# CMWX_LoRa_GPS_v14.net
KiCad netlist of a schematic drawn in EAGLE
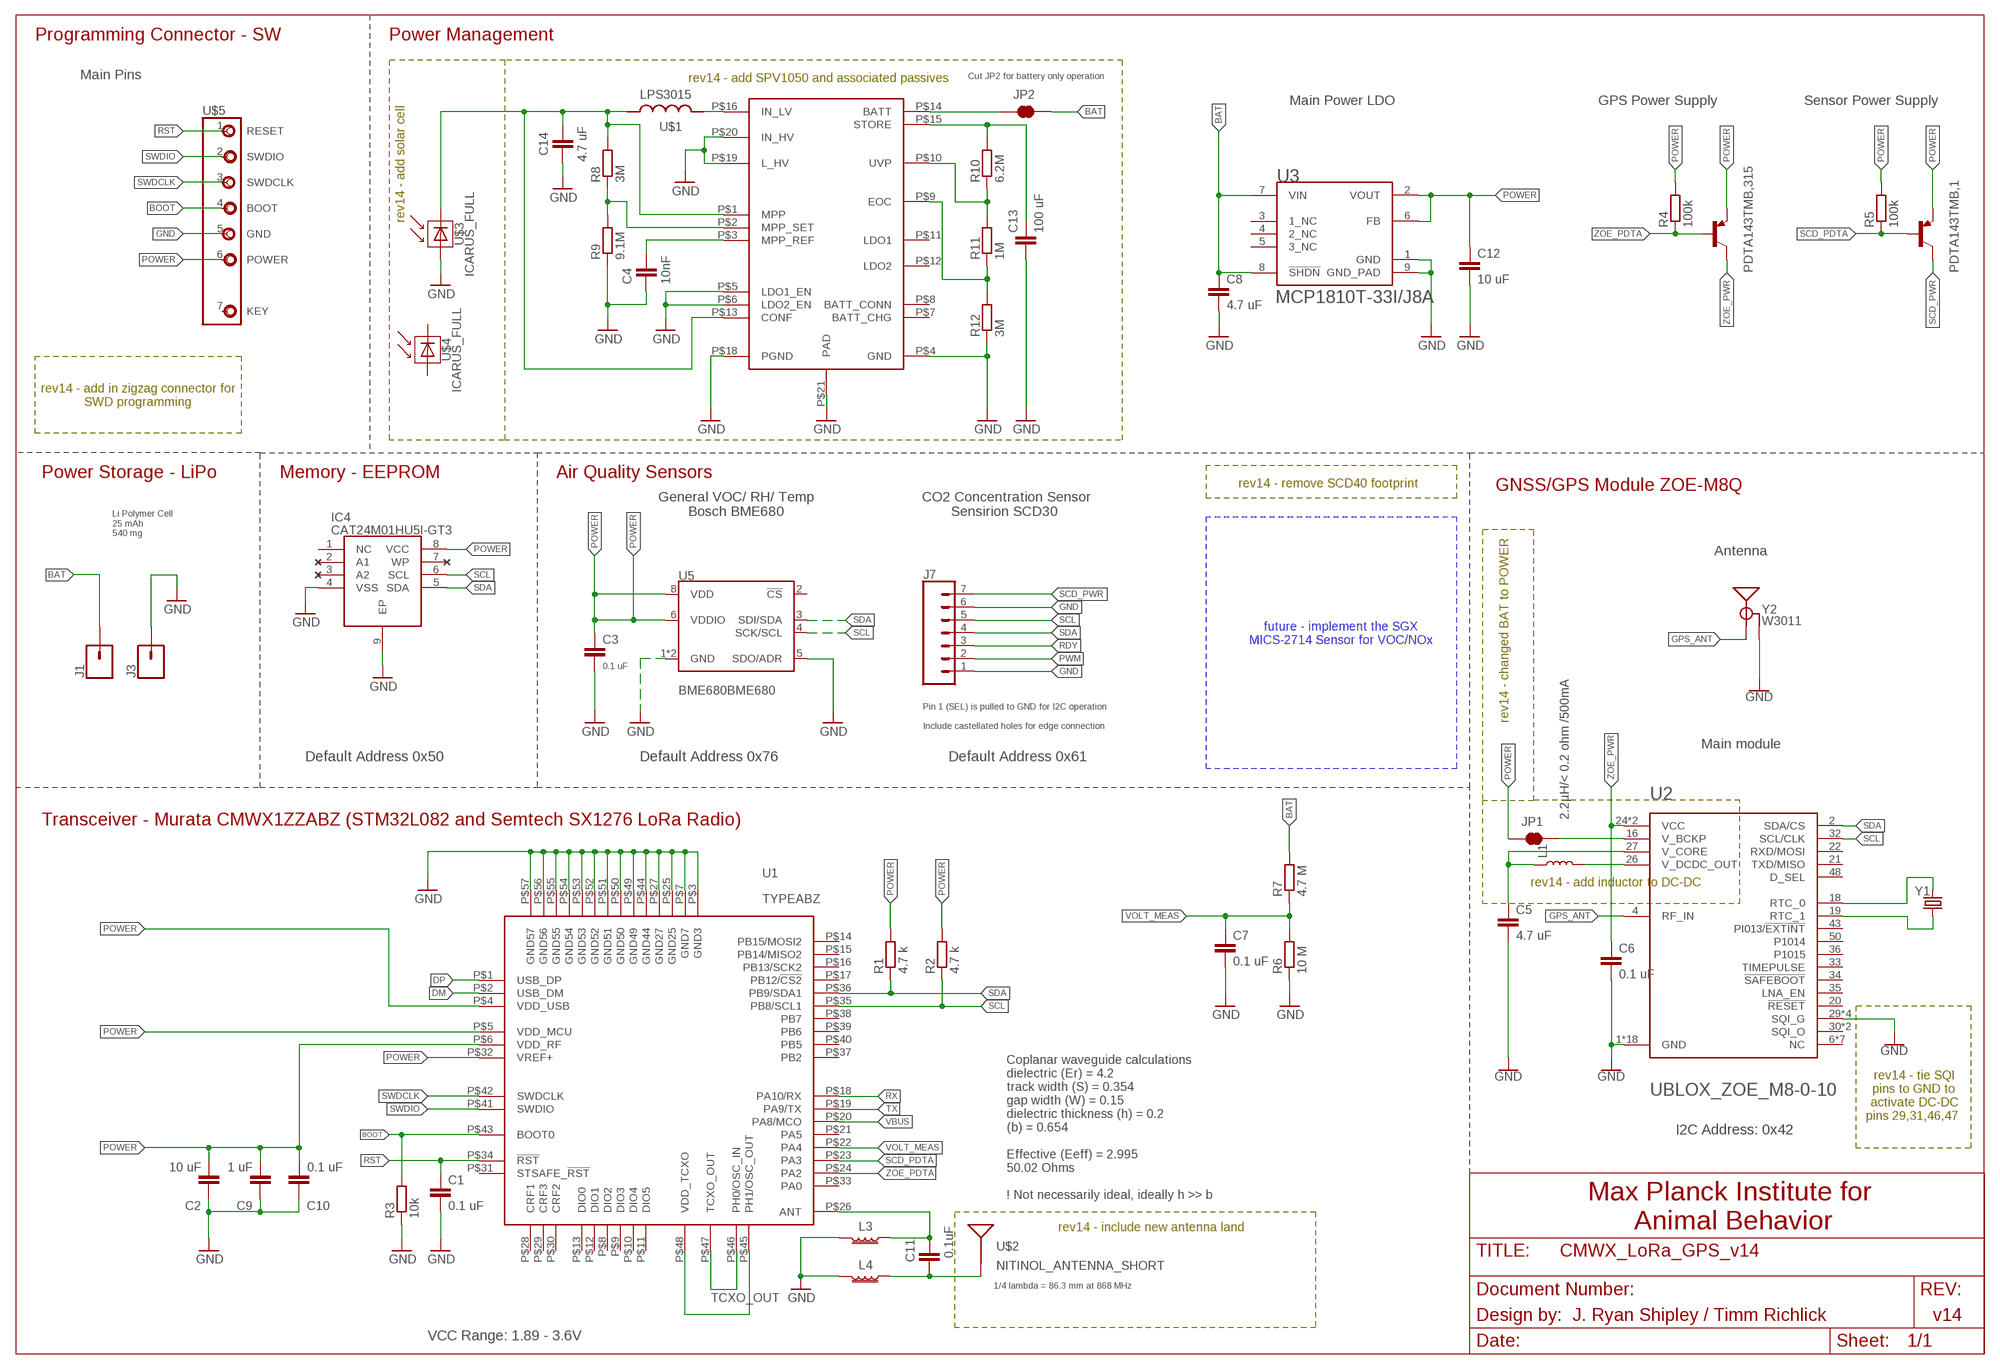
[diagram p0: schematic, sheet 1]

(export (version "E")
  (design (tool "Eeschema 10.0.6"))
  (components
    (comp (ref "C1")
      (value "0.1 uF")
      (footprint "eagle-import:C0201")
      (libsource (lib "eagle-import") (part "C-EUC0201"))
    )
    (comp (ref "C2")
      (value "10 uF")
      (footprint "eagle-import:C0201")
      (libsource (lib "eagle-import") (part "C-EUC0201"))
    )
    (comp (ref "C3")
      (value "0.1 uF")
      (footprint "eagle-import:C0201")
      (libsource (lib "eagle-import") (part "C-EUC0201"))
    )
    (comp (ref "C4")
      (value "10nF")
      (footprint "eagle-import:C0201")
      (libsource (lib "eagle-import") (part "C-EUC0201"))
    )
    (comp (ref "C5")
      (value "4.7 uF")
      (footprint "eagle-import:C0201")
      (libsource (lib "eagle-import") (part "C-EUC0201"))
    )
    (comp (ref "C6")
      (value "0.1 uF")
      (footprint "eagle-import:C0201")
      (libsource (lib "eagle-import") (part "C-EUC0201"))
    )
    (comp (ref "C7")
      (value "0.1 uF")
      (footprint "eagle-import:C0201")
      (libsource (lib "eagle-import") (part "C-EUC0201"))
    )
    (comp (ref "C8")
      (value "4.7 uF")
      (footprint "eagle-import:C0201")
      (libsource (lib "eagle-import") (part "C-EUC0201"))
    )
    (comp (ref "C9")
      (value "1 uF")
      (footprint "eagle-import:C0201")
      (libsource (lib "eagle-import") (part "C-EUC0201"))
    )
    (comp (ref "C10")
      (value "0.1 uF")
      (footprint "eagle-import:C0201")
      (libsource (lib "eagle-import") (part "C-EUC0201"))
    )
    (comp (ref "C11")
      (value "0.1uF")
      (footprint "eagle-import:0402-TIGHT")
      (libsource (lib "eagle-import") (part "0.1UF-0402T-16V-10%"))
    )
    (comp (ref "C12")
      (value "10 uF")
      (footprint "eagle-import:C0201")
      (libsource (lib "eagle-import") (part "C-EUC0201"))
    )
    (comp (ref "C13")
      (value "100 uF")
      (footprint "eagle-import:C0201")
      (libsource (lib "eagle-import") (part "C-EUC0201"))
    )
    (comp (ref "C14")
      (value "4.7 uF")
      (footprint "eagle-import:C0201")
      (libsource (lib "eagle-import") (part "C-EUC0201"))
    )
    (comp (ref "IC4")
      (value "CAT24M01HU5I-GT3")
      (footprint "eagle-import:SON50P300X200X55-9N")
      (fields
        (field (name "MOUSER_PART_NUMBER") "863-CAT24M01HU5I-GT3")
        (field (name "RS_PART_NUMBER") "7814831P")
      )
      (libsource (lib "eagle-import") (part "CAT24M01HU5I-GT3"))
    )
    (comp (ref "J1")
      (value "CONN_01PTH_NO_SILK_YES_STOP")
      (footprint "eagle-import:1X01_NO_SILK")
      (libsource (lib "eagle-import") (part "CONN_01PTH_NO_SILK_YES_STOP"))
    )
    (comp (ref "J3")
      (value "CONN_01PTH_NO_SILK_YES_STOP")
      (footprint "eagle-import:1X01_NO_SILK")
      (libsource (lib "eagle-import") (part "CONN_01PTH_NO_SILK_YES_STOP"))
    )
    (comp (ref "J7")
      (value "CONN_07NO_SILK")
      (footprint "eagle-import:1X07_NO_SILK")
      (libsource (lib "eagle-import") (part "CONN_07NO_SILK"))
    )
    (comp (ref "JP1")
      (value "JUMPER-SMT_2_NC_TRACE_NO-SILK")
      (footprint "eagle-import:SMT-JUMPER_2_NC_TRACE_NO-SILK")
      (libsource (lib "eagle-import") (part "JUMPER-SMT_2_NC_TRACE_NO-SILK"))
    )
    (comp (ref "JP2")
      (value "JUMPER-SMT_2_NC_TRACE_NO-SILK")
      (footprint "eagle-import:SMT-JUMPER_2_NC_TRACE_NO-SILK")
      (libsource (lib "eagle-import") (part "JUMPER-SMT_2_NC_TRACE_NO-SILK"))
    )
    (comp (ref "L1")
      (value "2.2µH/< 0.2 ohm /500mA")
      (footprint "eagle-import:0805")
      (libsource (lib "eagle-import") (part "INDUCTOR-0805-3.3UH"))
    )
    (comp (ref "L3")
      (value "FERRITE_BEAD-120_OHM_TIGHT")
      (footprint "eagle-import:0402-TIGHT")
      (libsource (lib "eagle-import") (part "FERRITE_BEAD-120_OHM_TIGHT"))
    )
    (comp (ref "L4")
      (value "FERRITE_BEAD-120_OHM_TIGHT")
      (footprint "eagle-import:0402-TIGHT")
      (libsource (lib "eagle-import") (part "FERRITE_BEAD-120_OHM_TIGHT"))
    )
    (comp (ref "PDTA143TMB,1")
      (value "TINYPICO-PNPAMB")
      (footprint "eagle-import:SOT883(B)")
      (libsource (lib "eagle-import") (part "TINYPICO-PNPMBA"))
    )
    (comp (ref "PDTA143TMB,315")
      (value "TINYPICO-PNPAMB")
      (footprint "eagle-import:SOT883(B)")
      (libsource (lib "eagle-import") (part "TINYPICO-PNPMBA"))
    )
    (comp (ref "R1")
      (value "4.7 k")
      (footprint "eagle-import:R0201")
      (libsource (lib "eagle-import") (part "R-EU_R0201"))
    )
    (comp (ref "R2")
      (value "4.7 k")
      (footprint "eagle-import:R0201")
      (libsource (lib "eagle-import") (part "R-EU_R0201"))
    )
    (comp (ref "R3")
      (value "10k")
      (footprint "eagle-import:R0201")
      (libsource (lib "eagle-import") (part "R-EU_R0201"))
    )
    (comp (ref "R4")
      (value "100k")
      (footprint "eagle-import:R0201")
      (libsource (lib "eagle-import") (part "R-EU_R0201"))
    )
    (comp (ref "R5")
      (value "100k")
      (footprint "eagle-import:R0201")
      (libsource (lib "eagle-import") (part "R-EU_R0201"))
    )
    (comp (ref "R6")
      (value "10 M")
      (footprint "eagle-import:R0201")
      (libsource (lib "eagle-import") (part "R-EU_R0201"))
    )
    (comp (ref "R7")
      (value "4.7 M")
      (footprint "eagle-import:R0201")
      (libsource (lib "eagle-import") (part "R-EU_R0201"))
    )
    (comp (ref "R8")
      (value "3M")
      (footprint "eagle-import:R0201")
      (libsource (lib "eagle-import") (part "R-EU_R0201"))
    )
    (comp (ref "R9")
      (value "9.1M")
      (footprint "eagle-import:R0201")
      (libsource (lib "eagle-import") (part "R-EU_R0201"))
    )
    (comp (ref "R10")
      (value "6.2M")
      (footprint "eagle-import:R0201")
      (libsource (lib "eagle-import") (part "R-EU_R0201"))
    )
    (comp (ref "R11")
      (value "1M")
      (footprint "eagle-import:R0201")
      (libsource (lib "eagle-import") (part "R-EU_R0201"))
    )
    (comp (ref "R12")
      (value "3M")
      (footprint "eagle-import:R0201")
      (libsource (lib "eagle-import") (part "R-EU_R0201"))
    )
    (comp (ref "U$1")
      (value "LPS3015")
      (footprint "eagle-import:LPS_3015")
      (libsource (lib "eagle-import") (part "LPS3015"))
    )
    (comp (ref "U$2")
      (value "NITINOL_ANTENNA_SHORT")
      (footprint "eagle-import:ICARUS_NITINOL_ANTENNA_SHORT")
      (libsource (lib "eagle-import") (part "NITINOL_ANTENNA_SHORT"))
    )
    (comp (ref "U$3")
      (value "ICARUS_FULL")
      (footprint "eagle-import:ICARUS_FULL")
      (libsource (lib "eagle-import") (part "ICARUS_FULL"))
    )
    (comp (ref "U$4")
      (value "ICARUS_FULL")
      (footprint "eagle-import:ICARUS_FULL")
      (libsource (lib "eagle-import") (part "ICARUS_FULL"))
    )
    (comp (ref "U$5")
      (value "ALBERT_ZIGZAG-ISP")
      (footprint "eagle-import:ALBERT_ZIGZAG-ISP")
      (libsource (lib "eagle-import") (part "ALBERT_ZIGZAG-ISP"))
    )
    (comp (ref "U1")
      (value "TYPEABZ")
      (footprint "eagle-import:TYPEABZ")
      (libsource (lib "eagle-import") (part "TYPEABZ"))
    )
    (comp (ref "U2")
      (value "UBLOX_ZOE_M8-0-10")
      (footprint "eagle-import:UBLOX_ZOE_M8-0-10")
      (libsource (lib "eagle-import") (part "UBLOX_ZOE_M8-0-10"))
    )
    (comp (ref "U3")
      (value "MICROCHIP_MCP1810T-33I-J8AMICROCHIP_MCP1810T-33I-J8A_0_0")
      (footprint "eagle-import:MICROCHIP_MCP1810T-33I-J8A_0")
      (fields
        (field (name "DIGIKEY_PART_NUMBER") "MCP1810T-33I/J8ACT-ND")
        (field (name "MF") "Microchip")
        (field (name "MOUSER_PART_NUMBER") "579-MCP1810T-33I/J8A")
      )
      (libsource (lib "eagle-import") (part "MICROCHIP_MCP1810T-33I-J8AMICROCHIP_MCP1810T-33I-J8A_0_0"))
    )
    (comp (ref "U4")
      (value "SPV1050")
      (footprint "eagle-import:SPV1050")
      (libsource (lib "eagle-import") (part "SPV1050"))
    )
    (comp (ref "U5")
      (value "BME680BME680")
      (footprint "eagle-import:LGA3.0X3.0")
      (libsource (lib "eagle-import") (part "BME680BME680"))
    )
    (comp (ref "Y1")
      (value "32.768kHz")
      (footprint "eagle-import:CRYSTAL-SMD-1.0X1.2MM")
      (libsource (lib "eagle-import") (part "CRYSTAL-32.768KHZ"))
    )
    (comp (ref "Y2")
      (value "W3011")
      (footprint "eagle-import:W3011")
      (libsource (lib "eagle-import") (part "GPS_CHIP_ANTENNAW3011"))
    )
  )
  (nets
    (net (code "1") (name "/TCXO_OUT") (class "Default")
      (node (ref "U1") (pin "P$46") (pinfunction "PH0/OSC_IN_P$46") (pintype "bidirectional"))
      (node (ref "U1") (pin "P$47") (pinfunction "TCXO_OUT_P$47") (pintype "bidirectional"))
    )
    (net (code "2") (name "BAT") (class "Default")
      (node (ref "C8") (pin "1") (pinfunction "1_1") (pintype "passive"))
      (node (ref "J1") (pin "1") (pinfunction "1_1") (pintype "passive"))
      (node (ref "JP2") (pin "2") (pinfunction "2_2") (pintype "passive"))
      (node (ref "R7") (pin "2") (pinfunction "2_2") (pintype "passive"))
      (node (ref "U3") (pin "7") (pinfunction "VIN_7") (pintype "bidirectional"))
      (node (ref "U3") (pin "8") (pinfunction "~{SHDN}_8") (pintype "bidirectional"))
    )
    (net (code "3") (name "BOOT") (class "Default")
      (node (ref "R3") (pin "2") (pinfunction "2_2") (pintype "passive"))
      (node (ref "U$5") (pin "4") (pinfunction "BOOT_4") (pintype "passive"))
      (node (ref "U1") (pin "P$43") (pinfunction "BOOT0_P$43") (pintype "bidirectional"))
    )
    (net (code "4") (name "DM") (class "Default")
      (node (ref "U1") (pin "P$2") (pinfunction "USB_DM_P$2") (pintype "bidirectional"))
    )
    (net (code "5") (name "DP") (class "Default")
      (node (ref "U1") (pin "P$1") (pinfunction "USB_DP_P$1") (pintype "bidirectional"))
    )
    (net (code "6") (name "GND") (class "Default")
      (node (ref "C1") (pin "2") (pinfunction "2_2") (pintype "passive"))
      (node (ref "C10") (pin "1") (pinfunction "1_1") (pintype "passive"))
      (node (ref "C12") (pin "2") (pinfunction "2_2") (pintype "passive"))
      (node (ref "C13") (pin "2") (pinfunction "2_2") (pintype "passive"))
      (node (ref "C14") (pin "2") (pinfunction "2_2") (pintype "passive"))
      (node (ref "C2") (pin "1") (pinfunction "1_1") (pintype "passive"))
      (node (ref "C3") (pin "2") (pinfunction "2_2") (pintype "passive"))
      (node (ref "C4") (pin "2") (pinfunction "2_2") (pintype "passive"))
      (node (ref "C5") (pin "2") (pinfunction "2_2") (pintype "passive"))
      (node (ref "C6") (pin "2") (pinfunction "2_2") (pintype "passive"))
      (node (ref "C7") (pin "2") (pinfunction "2_2") (pintype "passive"))
      (node (ref "C8") (pin "2") (pinfunction "2_2") (pintype "passive"))
      (node (ref "C9") (pin "1") (pinfunction "1_1") (pintype "passive"))
      (node (ref "IC4") (pin "4") (pinfunction "VSS_4") (pintype "power_in"))
      (node (ref "IC4") (pin "9") (pinfunction "EP_9") (pintype "bidirectional"))
      (node (ref "J3") (pin "1") (pinfunction "1_1") (pintype "passive"))
      (node (ref "J7") (pin "1") (pinfunction "1_1") (pintype "passive"))
      (node (ref "J7") (pin "6") (pinfunction "6_6") (pintype "passive"))
      (node (ref "L3") (pin "2") (pinfunction "2_2") (pintype "passive"))
      (node (ref "L4") (pin "2") (pinfunction "2_2") (pintype "passive"))
      (node (ref "R12") (pin "1") (pinfunction "1_1") (pintype "passive"))
      (node (ref "R3") (pin "1") (pinfunction "1_1") (pintype "passive"))
      (node (ref "R6") (pin "1") (pinfunction "1_1") (pintype "passive"))
      (node (ref "R9") (pin "1") (pinfunction "1_1") (pintype "passive"))
      (node (ref "U$3") (pin "P$2") (pinfunction "MINUS_P$2") (pintype "passive"))
      (node (ref "U$5") (pin "5") (pinfunction "GND_5") (pintype "passive"))
      (node (ref "U1") (pin "P$25") (pinfunction "GND25_P$25") (pintype "power_in"))
      (node (ref "U1") (pin "P$27") (pinfunction "GND27_P$27") (pintype "power_in"))
      (node (ref "U1") (pin "P$3") (pinfunction "GND3_P$3") (pintype "power_in"))
      (node (ref "U1") (pin "P$44") (pinfunction "GND44_P$44") (pintype "power_in"))
      (node (ref "U1") (pin "P$49") (pinfunction "GND49_P$49") (pintype "power_in"))
      (node (ref "U1") (pin "P$50") (pinfunction "GND50_P$50") (pintype "power_in"))
      (node (ref "U1") (pin "P$51") (pinfunction "GND51_P$51") (pintype "power_in"))
      (node (ref "U1") (pin "P$52") (pinfunction "GND52_P$52") (pintype "power_in"))
      (node (ref "U1") (pin "P$53") (pinfunction "GND53_P$53") (pintype "power_in"))
      (node (ref "U1") (pin "P$54") (pinfunction "GND54_P$54") (pintype "power_in"))
      (node (ref "U1") (pin "P$55") (pinfunction "GND55_P$55") (pintype "power_in"))
      (node (ref "U1") (pin "P$56") (pinfunction "GND56_P$56") (pintype "power_in"))
      (node (ref "U1") (pin "P$57") (pinfunction "GND57_P$57") (pintype "power_in"))
      (node (ref "U1") (pin "P$7") (pinfunction "GND7_P$7") (pintype "power_in"))
      (node (ref "U2") (pin "1") (pinfunction "GND_1") (pintype "power_in"))
      (node (ref "U2") (pin "10") (pinfunction "GND_10") (pintype "power_in"))
      (node (ref "U2") (pin "11") (pinfunction "GND_11") (pintype "power_in"))
      (node (ref "U2") (pin "12") (pinfunction "GND_12") (pintype "power_in"))
      (node (ref "U2") (pin "17") (pinfunction "GND_17") (pintype "power_in"))
      (node (ref "U2") (pin "23") (pinfunction "GND_23") (pintype "power_in"))
      (node (ref "U2") (pin "29") (pinfunction "SQI_G_29") (pintype "bidirectional"))
      (node (ref "U2") (pin "3") (pinfunction "GND_3") (pintype "power_in"))
      (node (ref "U2") (pin "31") (pinfunction "SQI_G_31") (pintype "bidirectional"))
      (node (ref "U2") (pin "37") (pinfunction "GND_37") (pintype "power_in"))
      (node (ref "U2") (pin "38") (pinfunction "GND_38") (pintype "power_in"))
      (node (ref "U2") (pin "39") (pinfunction "GND_39") (pintype "power_in"))
      (node (ref "U2") (pin "40") (pinfunction "GND_40") (pintype "power_in"))
      (node (ref "U2") (pin "41") (pinfunction "GND_41") (pintype "power_in"))
      (node (ref "U2") (pin "44") (pinfunction "GND_44") (pintype "power_in"))
      (node (ref "U2") (pin "46") (pinfunction "SQI_G_46") (pintype "bidirectional"))
      (node (ref "U2") (pin "47") (pinfunction "SQI_G_47") (pintype "bidirectional"))
      (node (ref "U2") (pin "49") (pinfunction "GND_49") (pintype "power_in"))
      (node (ref "U2") (pin "5") (pinfunction "GND_5") (pintype "power_in"))
      (node (ref "U2") (pin "7") (pinfunction "GND_7") (pintype "power_in"))
      (node (ref "U2") (pin "8") (pinfunction "GND_8") (pintype "power_in"))
      (node (ref "U2") (pin "9") (pinfunction "GND_9") (pintype "power_in"))
      (node (ref "U3") (pin "1") (pinfunction "GND_1") (pintype "bidirectional"))
      (node (ref "U3") (pin "9") (pinfunction "GND_PAD_9") (pintype "bidirectional"))
      (node (ref "U4") (pin "P$18") (pinfunction "PGND_P$18") (pintype "power_in"))
      (node (ref "U4") (pin "P$19") (pinfunction "L_HV_P$19") (pintype "power_in"))
      (node (ref "U4") (pin "P$20") (pinfunction "IN_HV_P$20") (pintype "power_in"))
      (node (ref "U4") (pin "P$21") (pinfunction "PAD_P$21") (pintype "power_in"))
      (node (ref "U4") (pin "P$4") (pinfunction "GND_P$4") (pintype "power_in"))
      (node (ref "U4") (pin "P$5") (pinfunction "LDO1_EN_P$5") (pintype "input"))
      (node (ref "U4") (pin "P$6") (pinfunction "LDO2_EN_P$6") (pintype "input"))
      (node (ref "U5") (pin "1") (pinfunction "GND_1") (pintype "bidirectional"))
      (node (ref "U5") (pin "5") (pinfunction "SDO/ADR_5") (pintype "bidirectional"))
      (node (ref "U5") (pin "7") (pinfunction "GND_7") (pintype "bidirectional"))
      (node (ref "Y2") (pin "2") (pinfunction "GND_2") (pintype "bidirectional"))
      (node (ref "Y2") (pin "3") (pinfunction "GND_3") (pintype "bidirectional"))
    )
    (net (code "7") (name "GPS_ANT") (class "Default")
      (node (ref "U2") (pin "4") (pinfunction "RF_IN_4") (pintype "bidirectional"))
      (node (ref "Y2") (pin "1") (pinfunction "SIGNAL_1") (pintype "bidirectional"))
    )
    (net (code "8") (name "Net-(C11-Pad1)") (class "Default")
      (node (ref "C11") (pin "1") (pinfunction "1_1") (pintype "passive"))
      (node (ref "L4") (pin "1") (pinfunction "1_1") (pintype "passive"))
      (node (ref "U$2") (pin "1") (pinfunction "SIGNAL_1") (pintype "bidirectional"))
      (node (ref "U$2") (pin "2") (pinfunction "SIGNAL_2") (pintype "bidirectional"))
      (node (ref "U$2") (pin "3") (pinfunction "SIGNAL_3") (pintype "bidirectional"))
    )
    (net (code "9") (name "Net-(U$1-1)") (class "Default")
      (node (ref "C14") (pin "1") (pinfunction "1_1") (pintype "passive"))
      (node (ref "R8") (pin "2") (pinfunction "2_2") (pintype "passive"))
      (node (ref "U$1") (pin "P$1") (pinfunction "1_P$1") (pintype "passive"))
      (node (ref "U$3") (pin "P$1") (pinfunction "PLUS_P$1") (pintype "passive"))
      (node (ref "U4") (pin "P$1") (pinfunction "MPP_P$1") (pintype "input"))
      (node (ref "U4") (pin "P$13") (pinfunction "CONF_P$13") (pintype "input"))
    )
    (net (code "10") (name "Net-(U$1-2)") (class "Default")
      (node (ref "U$1") (pin "P$2") (pinfunction "2_P$2") (pintype "passive"))
      (node (ref "U4") (pin "P$16") (pinfunction "IN_LV_P$16") (pintype "power_in"))
    )
    (net (code "11") (name "Net-(U1-ANT)") (class "Default")
      (node (ref "C11") (pin "2") (pinfunction "2_2") (pintype "passive"))
      (node (ref "L3") (pin "1") (pinfunction "1_1") (pintype "passive"))
      (node (ref "U1") (pin "P$26") (pinfunction "ANT_P$26") (pintype "bidirectional"))
    )
    (net (code "12") (name "Net-(U1-PH1{slash}OSC_OUT)") (class "Default")
      (node (ref "U1") (pin "P$45") (pinfunction "PH1/OSC_OUT_P$45") (pintype "bidirectional"))
      (node (ref "U1") (pin "P$48") (pinfunction "VDD_TCXO_P$48") (pintype "power_in"))
    )
    (net (code "13") (name "Net-(U2-RTC_0)") (class "Default")
      (node (ref "U2") (pin "18") (pinfunction "RTC_0_18") (pintype "bidirectional"))
      (node (ref "Y1") (pin "P$2") (pinfunction "2_P$2") (pintype "passive"))
    )
    (net (code "14") (name "Net-(U2-RTC_1)") (class "Default")
      (node (ref "U2") (pin "19") (pinfunction "RTC_1_19") (pintype "bidirectional"))
      (node (ref "Y1") (pin "P$1") (pinfunction "1_P$1") (pintype "passive"))
    )
    (net (code "15") (name "Net-(U2-V_BCKP)") (class "Default")
      (node (ref "JP1") (pin "2") (pinfunction "2_2") (pintype "passive"))
      (node (ref "U2") (pin "16") (pinfunction "V_BCKP_16") (pintype "power_in"))
    )
    (net (code "16") (name "Net-(U2-V_CORE)") (class "Default")
      (node (ref "C5") (pin "1") (pinfunction "1_1") (pintype "passive"))
      (node (ref "L1") (pin "1") (pinfunction "1_1") (pintype "passive"))
      (node (ref "U2") (pin "27") (pinfunction "V_CORE_27") (pintype "power_in"))
    )
    (net (code "17") (name "Net-(U2-V_DCDC_OUT)") (class "Default")
      (node (ref "L1") (pin "2") (pinfunction "2_2") (pintype "passive"))
      (node (ref "U2") (pin "26") (pinfunction "V_DCDC_OUT_26") (pintype "power_in"))
    )
    (net (code "18") (name "Net-(U4-BATT)") (class "Default")
      (node (ref "JP2") (pin "1") (pinfunction "1_1") (pintype "passive"))
      (node (ref "U4") (pin "P$14") (pinfunction "BATT_P$14") (pintype "bidirectional"))
    )
    (net (code "19") (name "Net-(U4-EOC)") (class "Default")
      (node (ref "R11") (pin "1") (pinfunction "1_1") (pintype "passive"))
      (node (ref "R12") (pin "2") (pinfunction "2_2") (pintype "passive"))
      (node (ref "U4") (pin "P$9") (pinfunction "EOC_P$9") (pintype "input"))
    )
    (net (code "20") (name "Net-(U4-MPP_REF)") (class "Default")
      (node (ref "C4") (pin "1") (pinfunction "1_1") (pintype "passive"))
      (node (ref "U4") (pin "P$3") (pinfunction "MPP_REF_P$3") (pintype "input"))
    )
    (net (code "21") (name "Net-(U4-MPP_SET)") (class "Default")
      (node (ref "R8") (pin "1") (pinfunction "1_1") (pintype "passive"))
      (node (ref "R9") (pin "2") (pinfunction "2_2") (pintype "passive"))
      (node (ref "U4") (pin "P$2") (pinfunction "MPP_SET_P$2") (pintype "input"))
    )
    (net (code "22") (name "Net-(U4-STORE)") (class "Default")
      (node (ref "C13") (pin "1") (pinfunction "1_1") (pintype "passive"))
      (node (ref "R10") (pin "2") (pinfunction "2_2") (pintype "passive"))
      (node (ref "U4") (pin "P$15") (pinfunction "STORE_P$15") (pintype "bidirectional"))
    )
    (net (code "23") (name "Net-(U4-UVP)") (class "Default")
      (node (ref "R10") (pin "1") (pinfunction "1_1") (pintype "passive"))
      (node (ref "R11") (pin "2") (pinfunction "2_2") (pintype "passive"))
      (node (ref "U4") (pin "P$10") (pinfunction "UVP_P$10") (pintype "input"))
    )
    (net (code "24") (name "POWER") (class "Default")
      (node (ref "C10") (pin "2") (pinfunction "2_2") (pintype "passive"))
      (node (ref "C12") (pin "1") (pinfunction "1_1") (pintype "passive"))
      (node (ref "C2") (pin "2") (pinfunction "2_2") (pintype "passive"))
      (node (ref "C3") (pin "1") (pinfunction "1_1") (pintype "passive"))
      (node (ref "C9") (pin "2") (pinfunction "2_2") (pintype "passive"))
      (node (ref "IC4") (pin "8") (pinfunction "VCC_8") (pintype "power_in"))
      (node (ref "JP1") (pin "1") (pinfunction "1_1") (pintype "passive"))
      (node (ref "PDTA143TMB,1") (pin "2") (pinfunction "E_2") (pintype "passive"))
      (node (ref "PDTA143TMB,315") (pin "2") (pinfunction "E_2") (pintype "passive"))
      (node (ref "R1") (pin "2") (pinfunction "2_2") (pintype "passive"))
      (node (ref "R2") (pin "2") (pinfunction "2_2") (pintype "passive"))
      (node (ref "R4") (pin "2") (pinfunction "2_2") (pintype "passive"))
      (node (ref "R5") (pin "2") (pinfunction "2_2") (pintype "passive"))
      (node (ref "U$5") (pin "6") (pinfunction "POWER_6") (pintype "passive"))
      (node (ref "U1") (pin "P$32") (pinfunction "VREF+_P$32") (pintype "power_in"))
      (node (ref "U1") (pin "P$4") (pinfunction "VDD_USB_P$4") (pintype "power_in"))
      (node (ref "U1") (pin "P$5") (pinfunction "VDD_MCU_P$5") (pintype "power_in"))
      (node (ref "U1") (pin "P$6") (pinfunction "VDD_RF_P$6") (pintype "power_in"))
      (node (ref "U3") (pin "2") (pinfunction "VOUT_2") (pintype "bidirectional"))
      (node (ref "U3") (pin "6") (pinfunction "FB_6") (pintype "bidirectional"))
      (node (ref "U5") (pin "6") (pinfunction "VDDIO_6") (pintype "bidirectional"))
      (node (ref "U5") (pin "8") (pinfunction "VDD_8") (pintype "bidirectional"))
    )
    (net (code "25") (name "PWM") (class "Default")
      (node (ref "J7") (pin "2") (pinfunction "2_2") (pintype "passive"))
    )
    (net (code "26") (name "RDY") (class "Default")
      (node (ref "J7") (pin "3") (pinfunction "3_3") (pintype "passive"))
    )
    (net (code "27") (name "RST") (class "Default")
      (node (ref "C1") (pin "1") (pinfunction "1_1") (pintype "passive"))
      (node (ref "U$5") (pin "1") (pinfunction "RESET_1") (pintype "passive"))
      (node (ref "U1") (pin "P$34") (pinfunction "~{RST}_P$34") (pintype "bidirectional"))
    )
    (net (code "28") (name "RX") (class "Default")
      (node (ref "U1") (pin "P$18") (pinfunction "PA10/RX_P$18") (pintype "bidirectional"))
    )
    (net (code "29") (name "SCD_PDTA") (class "Default")
      (node (ref "PDTA143TMB,1") (pin "1") (pinfunction "B_1") (pintype "passive"))
      (node (ref "R5") (pin "1") (pinfunction "1_1") (pintype "passive"))
      (node (ref "U1") (pin "P$23") (pinfunction "PA3_P$23") (pintype "bidirectional"))
    )
    (net (code "30") (name "SCD_PWR") (class "Default")
      (node (ref "J7") (pin "7") (pinfunction "7_7") (pintype "passive"))
      (node (ref "PDTA143TMB,1") (pin "3") (pinfunction "C_3") (pintype "passive"))
    )
    (net (code "31") (name "SCL") (class "Default")
      (node (ref "IC4") (pin "6") (pinfunction "SCL_6") (pintype "bidirectional"))
      (node (ref "J7") (pin "5") (pinfunction "5_5") (pintype "passive"))
      (node (ref "R2") (pin "1") (pinfunction "1_1") (pintype "passive"))
      (node (ref "U1") (pin "P$35") (pinfunction "PB8/SCL1_P$35") (pintype "bidirectional"))
      (node (ref "U2") (pin "32") (pinfunction "SCL/CLK_32") (pintype "bidirectional"))
      (node (ref "U5") (pin "4") (pinfunction "SCK/SCL_4") (pintype "bidirectional"))
    )
    (net (code "32") (name "SDA") (class "Default")
      (node (ref "IC4") (pin "5") (pinfunction "SDA_5") (pintype "bidirectional"))
      (node (ref "J7") (pin "4") (pinfunction "4_4") (pintype "passive"))
      (node (ref "R1") (pin "1") (pinfunction "1_1") (pintype "passive"))
      (node (ref "U1") (pin "P$36") (pinfunction "PB9/SDA1_P$36") (pintype "bidirectional"))
      (node (ref "U2") (pin "2") (pinfunction "SDA/CS_2") (pintype "bidirectional"))
      (node (ref "U5") (pin "3") (pinfunction "SDI/SDA_3") (pintype "bidirectional"))
    )
    (net (code "33") (name "SWDCLK") (class "Default")
      (node (ref "U$5") (pin "3") (pinfunction "SWDCLK_3") (pintype "passive"))
      (node (ref "U1") (pin "P$42") (pinfunction "SWDCLK_P$42") (pintype "bidirectional"))
    )
    (net (code "34") (name "SWDIO") (class "Default")
      (node (ref "U$5") (pin "2") (pinfunction "SWDIO_2") (pintype "passive"))
      (node (ref "U1") (pin "P$41") (pinfunction "SWDIO_P$41") (pintype "bidirectional"))
    )
    (net (code "35") (name "TX") (class "Default")
      (node (ref "U1") (pin "P$19") (pinfunction "PA9/TX_P$19") (pintype "bidirectional"))
    )
    (net (code "36") (name "VBUS") (class "Default")
      (node (ref "U1") (pin "P$20") (pinfunction "PA8/MCO_P$20") (pintype "bidirectional"))
    )
    (net (code "37") (name "VOLT_MEAS") (class "Default")
      (node (ref "C7") (pin "1") (pinfunction "1_1") (pintype "passive"))
      (node (ref "R6") (pin "2") (pinfunction "2_2") (pintype "passive"))
      (node (ref "R7") (pin "1") (pinfunction "1_1") (pintype "passive"))
      (node (ref "U1") (pin "P$22") (pinfunction "PA4_P$22") (pintype "bidirectional"))
    )
    (net (code "38") (name "ZOE_PDTA") (class "Default")
      (node (ref "PDTA143TMB,315") (pin "1") (pinfunction "B_1") (pintype "passive"))
      (node (ref "R4") (pin "1") (pinfunction "1_1") (pintype "passive"))
      (node (ref "U1") (pin "P$24") (pinfunction "PA2_P$24") (pintype "bidirectional"))
    )
    (net (code "39") (name "ZOE_PWR") (class "Default")
      (node (ref "C6") (pin "1") (pinfunction "1_1") (pintype "passive"))
      (node (ref "PDTA143TMB,315") (pin "3") (pinfunction "C_3") (pintype "passive"))
      (node (ref "U2") (pin "24") (pinfunction "VCC_24") (pintype "power_in"))
      (node (ref "U2") (pin "25") (pinfunction "VCC_25") (pintype "power_in"))
    )
    (net (code "40") (name "unconnected-(IC4-A1-Pad2)") (class "Default")
      (node (ref "IC4") (pin "2") (pinfunction "A1_2") (pintype "bidirectional"))
    )
    (net (code "41") (name "unconnected-(IC4-A2-Pad3)") (class "Default")
      (node (ref "IC4") (pin "3") (pinfunction "A2_3") (pintype "bidirectional"))
    )
    (net (code "42") (name "unconnected-(IC4-NC-Pad1)") (class "Default")
      (node (ref "IC4") (pin "1") (pinfunction "NC_1") (pintype "no_connect"))
    )
    (net (code "43") (name "unconnected-(IC4-WP-Pad7)") (class "Default")
      (node (ref "IC4") (pin "7") (pinfunction "WP_7") (pintype "bidirectional"))
    )
    (net (code "44") (name "unconnected-(U$4-MINUS-PadP$2)") (class "Default")
      (node (ref "U$4") (pin "P$2") (pinfunction "MINUS_P$2") (pintype "passive"))
    )
    (net (code "45") (name "unconnected-(U$4-PLUS-PadP$1)") (class "Default")
      (node (ref "U$4") (pin "P$1") (pinfunction "PLUS_P$1") (pintype "passive"))
    )
    (net (code "46") (name "unconnected-(U$5-KEY-Pad7)") (class "Default")
      (node (ref "U$5") (pin "7") (pinfunction "KEY_7") (pintype "passive"))
    )
    (net (code "47") (name "unconnected-(U1-CRF1-PadP$28)") (class "Default")
      (node (ref "U1") (pin "P$28") (pinfunction "CRF1_P$28") (pintype "no_connect"))
    )
    (net (code "48") (name "unconnected-(U1-CRF2-PadP$30)") (class "Default")
      (node (ref "U1") (pin "P$30") (pinfunction "CRF2_P$30") (pintype "no_connect"))
    )
    (net (code "49") (name "unconnected-(U1-CRF3-PadP$29)") (class "Default")
      (node (ref "U1") (pin "P$29") (pinfunction "CRF3_P$29") (pintype "no_connect"))
    )
    (net (code "50") (name "unconnected-(U1-DIO0-PadP$13)") (class "Default")
      (node (ref "U1") (pin "P$13") (pinfunction "DIO0_P$13") (pintype "no_connect"))
    )
    (net (code "51") (name "unconnected-(U1-DIO1-PadP$12)") (class "Default")
      (node (ref "U1") (pin "P$12") (pinfunction "DIO1_P$12") (pintype "no_connect"))
    )
    (net (code "52") (name "unconnected-(U1-DIO2-PadP$8)") (class "Default")
      (node (ref "U1") (pin "P$8") (pinfunction "DIO2_P$8") (pintype "no_connect"))
    )
    (net (code "53") (name "unconnected-(U1-DIO3-PadP$9)") (class "Default")
      (node (ref "U1") (pin "P$9") (pinfunction "DIO3_P$9") (pintype "no_connect"))
    )
    (net (code "54") (name "unconnected-(U1-DIO4-PadP$10)") (class "Default")
      (node (ref "U1") (pin "P$10") (pinfunction "DIO4_P$10") (pintype "bidirectional"))
    )
    (net (code "55") (name "unconnected-(U1-DIO5-PadP$11)") (class "Default")
      (node (ref "U1") (pin "P$11") (pinfunction "DIO5_P$11") (pintype "bidirectional"))
    )
    (net (code "56") (name "unconnected-(U1-PA0-PadP$33)") (class "Default")
      (node (ref "U1") (pin "P$33") (pinfunction "PA0_P$33") (pintype "bidirectional"))
    )
    (net (code "57") (name "unconnected-(U1-PA5-PadP$21)") (class "Default")
      (node (ref "U1") (pin "P$21") (pinfunction "PA5_P$21") (pintype "bidirectional"))
    )
    (net (code "58") (name "unconnected-(U1-PB2-PadP$37)") (class "Default")
      (node (ref "U1") (pin "P$37") (pinfunction "PB2_P$37") (pintype "bidirectional"))
    )
    (net (code "59") (name "unconnected-(U1-PB5-PadP$40)") (class "Default")
      (node (ref "U1") (pin "P$40") (pinfunction "PB5_P$40") (pintype "bidirectional"))
    )
    (net (code "60") (name "unconnected-(U1-PB6-PadP$39)") (class "Default")
      (node (ref "U1") (pin "P$39") (pinfunction "PB6_P$39") (pintype "bidirectional"))
    )
    (net (code "61") (name "unconnected-(U1-PB7-PadP$38)") (class "Default")
      (node (ref "U1") (pin "P$38") (pinfunction "PB7_P$38") (pintype "bidirectional"))
    )
    (net (code "62") (name "unconnected-(U1-PB12{slash}~{CS2}-PadP$17)") (class "Default")
      (node (ref "U1") (pin "P$17") (pinfunction "PB12/~{CS2}_P$17") (pintype "bidirectional"))
    )
    (net (code "63") (name "unconnected-(U1-PB13{slash}SCK2-PadP$16)") (class "Default")
      (node (ref "U1") (pin "P$16") (pinfunction "PB13/SCK2_P$16") (pintype "bidirectional"))
    )
    (net (code "64") (name "unconnected-(U1-PB14{slash}MISO2-PadP$15)") (class "Default")
      (node (ref "U1") (pin "P$15") (pinfunction "PB14/MISO2_P$15") (pintype "bidirectional"))
    )
    (net (code "65") (name "unconnected-(U1-PB15{slash}MOSI2-PadP$14)") (class "Default")
      (node (ref "U1") (pin "P$14") (pinfunction "PB15/MOSI2_P$14") (pintype "bidirectional"))
    )
    (net (code "66") (name "unconnected-(U1-STSAFE_~{RST}-PadP$31)") (class "Default")
      (node (ref "U1") (pin "P$31") (pinfunction "STSAFE_~{RST}_P$31") (pintype "bidirectional"))
    )
    (net (code "67") (name "unconnected-(U2-D_SEL-Pad48)") (class "Default")
      (node (ref "U2") (pin "48") (pinfunction "D_SEL_48") (pintype "bidirectional"))
    )
    (net (code "68") (name "unconnected-(U2-LNA_EN-Pad35)") (class "Default")
      (node (ref "U2") (pin "35") (pinfunction "LNA_EN_35") (pintype "bidirectional"))
    )
    (net (code "69") (name "unconnected-(U2-NC-Pad6)") (class "Default")
      (node (ref "U2") (pin "6") (pinfunction "NC_6") (pintype "no_connect"))
    )
    (net (code "70") (name "unconnected-(U2-NC-Pad13)") (class "Default")
      (node (ref "U2") (pin "13") (pinfunction "NC_13") (pintype "no_connect"))
    )
    (net (code "71") (name "unconnected-(U2-NC-Pad14)") (class "Default")
      (node (ref "U2") (pin "14") (pinfunction "NC_14") (pintype "no_connect"))
    )
    (net (code "72") (name "unconnected-(U2-NC-Pad15)") (class "Default")
      (node (ref "U2") (pin "15") (pinfunction "NC_15") (pintype "no_connect"))
    )
    (net (code "73") (name "unconnected-(U2-NC-Pad28)") (class "Default")
      (node (ref "U2") (pin "28") (pinfunction "NC_28") (pintype "no_connect"))
    )
    (net (code "74") (name "unconnected-(U2-NC-Pad42)") (class "Default")
      (node (ref "U2") (pin "42") (pinfunction "NC_42") (pintype "no_connect"))
    )
    (net (code "75") (name "unconnected-(U2-NC-Pad51)") (class "Default")
      (node (ref "U2") (pin "51") (pinfunction "NC_51") (pintype "no_connect"))
    )
    (net (code "76") (name "unconnected-(U2-P1014-Pad50)") (class "Default")
      (node (ref "U2") (pin "50") (pinfunction "P1014_50") (pintype "bidirectional"))
    )
    (net (code "77") (name "unconnected-(U2-P1015-Pad36)") (class "Default")
      (node (ref "U2") (pin "36") (pinfunction "P1015_36") (pintype "bidirectional"))
    )
    (net (code "78") (name "unconnected-(U2-PI013{slash}~{EXTINT}-Pad43)") (class "Default")
      (node (ref "U2") (pin "43") (pinfunction "PI013/~{EXTINT}_43") (pintype "bidirectional"))
    )
    (net (code "79") (name "unconnected-(U2-RXD{slash}MOSI-Pad22)") (class "Default")
      (node (ref "U2") (pin "22") (pinfunction "RXD/MOSI_22") (pintype "bidirectional"))
    )
    (net (code "80") (name "unconnected-(U2-SQI_O-Pad30)") (class "Default")
      (node (ref "U2") (pin "30") (pinfunction "SQI_O_30") (pintype "no_connect"))
    )
    (net (code "81") (name "unconnected-(U2-SQI_O-Pad45)") (class "Default")
      (node (ref "U2") (pin "45") (pinfunction "SQI_O_45") (pintype "no_connect"))
    )
    (net (code "82") (name "unconnected-(U2-TIMEPULSE-Pad33)") (class "Default")
      (node (ref "U2") (pin "33") (pinfunction "TIMEPULSE_33") (pintype "bidirectional"))
    )
    (net (code "83") (name "unconnected-(U2-TXD{slash}MISO-Pad21)") (class "Default")
      (node (ref "U2") (pin "21") (pinfunction "TXD/MISO_21") (pintype "bidirectional"))
    )
    (net (code "84") (name "unconnected-(U2-~{RESET}-Pad20)") (class "Default")
      (node (ref "U2") (pin "20") (pinfunction "~{RESET}_20") (pintype "bidirectional"))
    )
    (net (code "85") (name "unconnected-(U2-~{SAFEBOOT}-Pad34)") (class "Default")
      (node (ref "U2") (pin "34") (pinfunction "~{SAFEBOOT}_34") (pintype "bidirectional"))
    )
    (net (code "86") (name "unconnected-(U3-1_NC-Pad3)") (class "Default")
      (node (ref "U3") (pin "3") (pinfunction "1_NC_3") (pintype "bidirectional"))
    )
    (net (code "87") (name "unconnected-(U3-2_NC-Pad4)") (class "Default")
      (node (ref "U3") (pin "4") (pinfunction "2_NC_4") (pintype "bidirectional"))
    )
    (net (code "88") (name "unconnected-(U3-3_NC-Pad5)") (class "Default")
      (node (ref "U3") (pin "5") (pinfunction "3_NC_5") (pintype "bidirectional"))
    )
    (net (code "89") (name "unconnected-(U4-BATT_CHG-PadP$7)") (class "Default")
      (node (ref "U4") (pin "P$7") (pinfunction "BATT_CHG_P$7") (pintype "open_collector"))
    )
    (net (code "90") (name "unconnected-(U4-BATT_CONN-PadP$8)") (class "Default")
      (node (ref "U4") (pin "P$8") (pinfunction "BATT_CONN_P$8") (pintype "open_collector"))
    )
    (net (code "91") (name "unconnected-(U4-LDO1-PadP$11)") (class "Default")
      (node (ref "U4") (pin "P$11") (pinfunction "LDO1_P$11") (pintype "output"))
    )
    (net (code "92") (name "unconnected-(U4-LDO2-PadP$12)") (class "Default")
      (node (ref "U4") (pin "P$12") (pinfunction "LDO2_P$12") (pintype "output"))
    )
    (net (code "93") (name "unconnected-(U5-~{CS}-Pad2)") (class "Default")
      (node (ref "U5") (pin "2") (pinfunction "~{CS}_2") (pintype "bidirectional"))
    )
  )
)
